# Emitter.net
KiCad netlist of a schematic drawn in Altium Designer
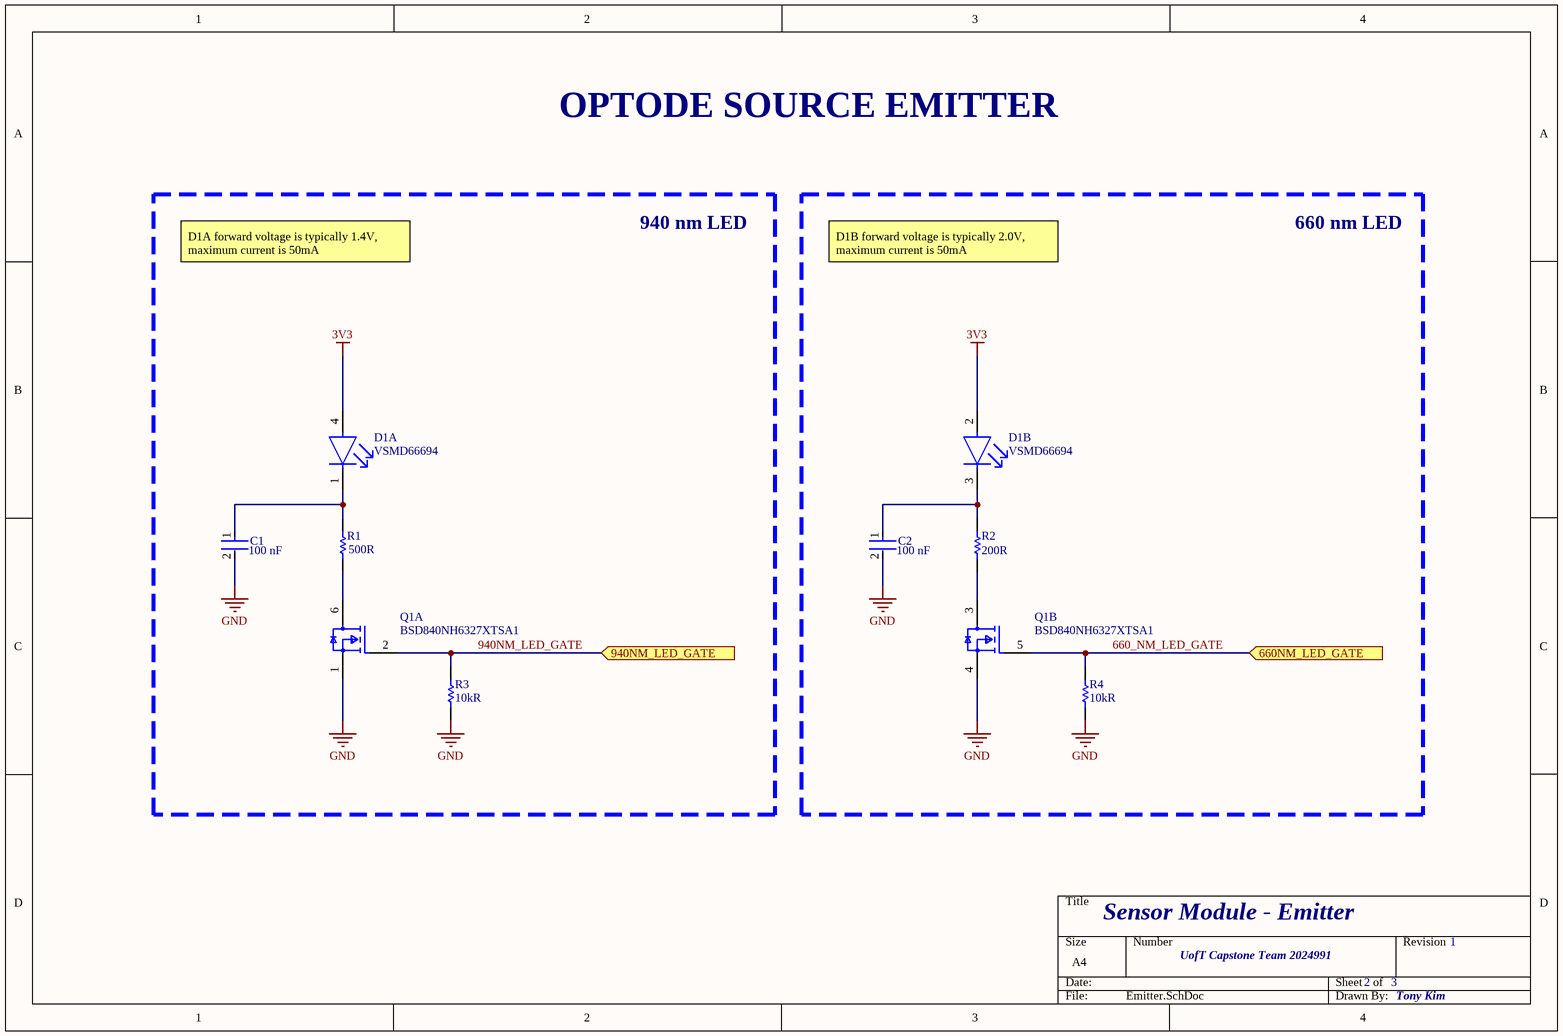
[diagram p0: Emitter.SchDoc]

(export (version "E")
  (design (tool "Eeschema 10.0.6"))
  (components
    (comp (ref "C1")
      (value "CC0603KRX7R7BB104")
      (footprint "FP-CC0603-DA-MFG")
      (description "CAP CER 0.1UF 16V X7R 0603")
      (fields
        (field (name "OCTOPART") "https://octopart.com/cc0603krx7r7bb104-yageo-192941")
        (field (name "TOLERANCE") "0.1")
        (field (name "CAPACITANCE") "100 nF")
      )
      (libsource (lib "Altium Content Vault") (part "11868f565c42a9108669ba33697ecf6"))
    )
    (comp (ref "C2")
      (value "CC0603KRX7R7BB104")
      (footprint "FP-CC0603-DA-MFG")
      (description "CAP CER 0.1UF 16V X7R 0603")
      (fields
        (field (name "OCTOPART") "https://octopart.com/cc0603krx7r7bb104-yageo-192941")
        (field (name "TOLERANCE") "0.1")
        (field (name "CAPACITANCE") "100 nF")
      )
      (libsource (lib "Altium Content Vault") (part "11868f565c42a9108669ba33697ecf6"))
    )
    (comp (ref "D1")
      (value "VSMD66694")
      (footprint "FP-6_550-5347_01-4-MFG")
      (description "EMITTER DUAL 660/940NM SQURE PCB")
      (fields
        (field (name "MANUFACTURER") "Vishay Semiconductor Opto Division")
        (field (name "OCTOPART") "https://octopart.com/vsmd66694-vishay-74221794")
      )
      (libsource (lib "Altium Content Vault") (part "f63fdef09506549d47f9c99805bef80"))
    )
    (comp (ref "Q1")
      (value "BSD840NH6327XTSA1")
      (footprint "FP-PG-SOT363-6-MFG")
      (description "MOSFET 2N-CH 20V 0.88A SOT363")
      (libsource (lib "Altium Content Vault") (part "6559164231102c4ec4f565336d3f230"))
    )
    (comp (ref "R1")
      (value "RK73H1JTTD38R3F")
      (footprint "RESC1608X55X30LL20T10")
      (fields (field (name "MANUFACTURER") "KOA Speer"))
      (libsource (lib "Altium Content Vault") (part "RES"))
    )
    (comp (ref "R2")
      (value "CRCW0603200RJNEA")
      (footprint "RESC1609X50X30NL10T20")
      (fields (field (name "MANUFACTURER") "Vishay Dale") (field (name "RESISTANCE") "200R"))
      (libsource (lib "Altium Content Vault") (part "RES"))
    )
    (comp (ref "R3")
      (value "CRCW060310K0FKEA")
      (footprint "RESC1609X50X30NL8T20")
      (description "Chip Resistor, 10 KOhm, +/- 1%, 100 mW, -55 to 155 degC, 0603 (1608 Metric), RoHS, Tape and Reel")
      (fields (field (name "MANUFACTURER") "Vishay Semiconductor") (field (name "RESISTANCE") "10kR"))
      (libsource (lib "Altium Content Vault") (part "RES-2"))
    )
    (comp (ref "R4")
      (value "CRCW060310K0FKEA")
      (footprint "RESC1609X50X30NL8T20")
      (description "Chip Resistor, 10 KOhm, +/- 1%, 100 mW, -55 to 155 degC, 0603 (1608 Metric), RoHS, Tape and Reel")
      (fields (field (name "MANUFACTURER") "Vishay Semiconductor") (field (name "RESISTANCE") "10kR"))
      (libsource (lib "Altium Content Vault") (part "RES-2"))
    )
  )
  (nets
    (net (code "1") (name "/660_NM_LED_GATE") (class "Default")
      (node (ref "Q1") (pin "5") (pinfunction "2_GATE_5") (pintype "passive"))
      (node (ref "R4") (pin "2") (pinfunction "2_2") (pintype "passive"))
    )
    (net (code "2") (name "/940NM_LED_GATE") (class "Default")
      (node (ref "Q1") (pin "2") (pinfunction "1_GATE_2") (pintype "passive"))
      (node (ref "R3") (pin "2") (pinfunction "2_2") (pintype "passive"))
    )
    (net (code "3") (name "3V3") (class "Default")
      (node (ref "D1") (pin "2") (pinfunction "RED_A_2") (pintype "passive"))
      (node (ref "D1") (pin "4") (pinfunction "IR_anode_4") (pintype "passive"))
    )
    (net (code "4") (name "GND") (class "Default")
      (node (ref "C1") (pin "2") (pinfunction "2_2") (pintype "passive"))
      (node (ref "C2") (pin "2") (pinfunction "2_2") (pintype "passive"))
      (node (ref "Q1") (pin "1") (pinfunction "1_SOURCE_1") (pintype "passive"))
      (node (ref "Q1") (pin "4") (pinfunction "2_SOURCE_4") (pintype "passive"))
      (node (ref "R3") (pin "1") (pinfunction "1_1") (pintype "passive"))
      (node (ref "R4") (pin "1") (pinfunction "1_1") (pintype "passive"))
    )
    (net (code "5") (name "Net-(D1A-IR_cathode)") (class "Default")
      (node (ref "C1") (pin "1") (pinfunction "1_1") (pintype "passive"))
      (node (ref "D1") (pin "1") (pinfunction "IR_cathode_1") (pintype "passive"))
      (node (ref "R1") (pin "2") (pinfunction "2_2") (pintype "passive"))
    )
    (net (code "6") (name "Net-(D1B-RED_C)") (class "Default")
      (node (ref "C2") (pin "1") (pinfunction "1_1") (pintype "passive"))
      (node (ref "D1") (pin "3") (pinfunction "RED_C_3") (pintype "passive"))
      (node (ref "R2") (pin "2") (pinfunction "2_2") (pintype "passive"))
    )
    (net (code "7") (name "Net-(Q1A-1_DRAIN)") (class "Default")
      (node (ref "Q1") (pin "6") (pinfunction "1_DRAIN_6") (pintype "passive"))
      (node (ref "R1") (pin "1") (pinfunction "1_1") (pintype "passive"))
    )
    (net (code "8") (name "Net-(Q1B-2_DRAIN)") (class "Default")
      (node (ref "Q1") (pin "3") (pinfunction "2_DRAIN_3") (pintype "passive"))
      (node (ref "R2") (pin "1") (pinfunction "1_1") (pintype "passive"))
    )
  )
)
